# Industrial-Controller_MCU.net
KiCad netlist of a schematic drawn in Altium Designer
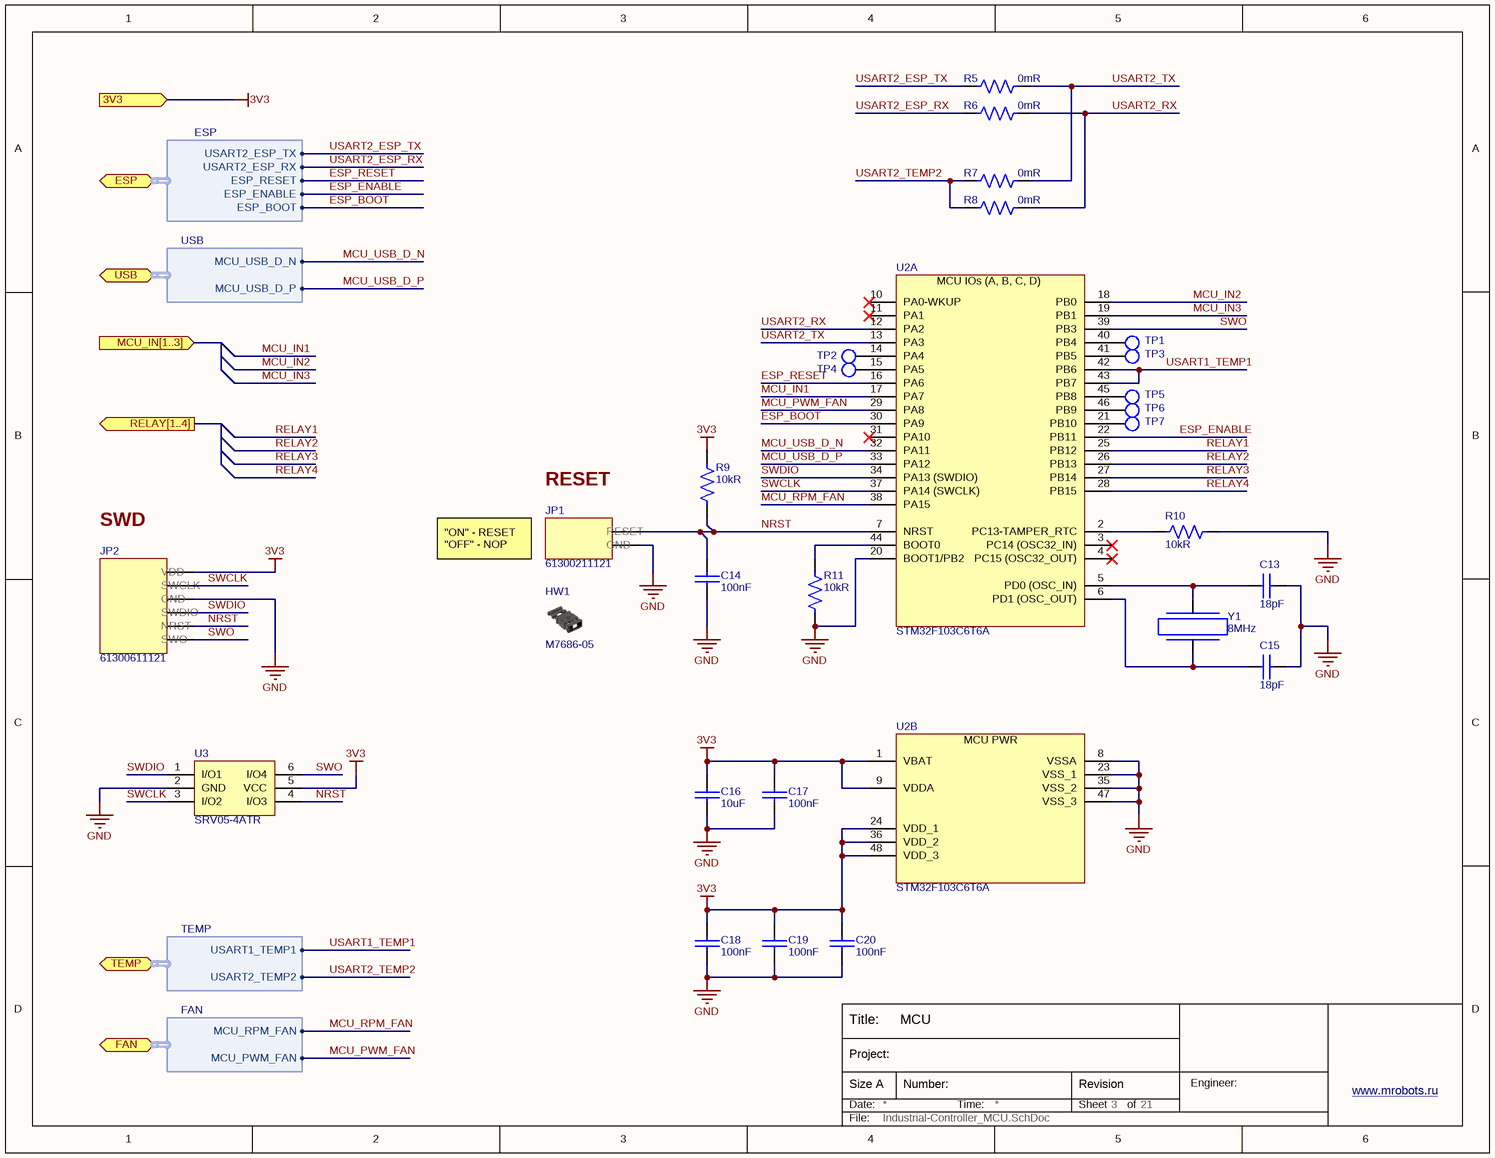
[diagram p0: Industrial-Controller_MCU.SchDoc]

(export (version "E")
  (design (tool "Eeschema 10.0.6"))
  (components
    (comp (ref "C13")
      (value "18pF")
      (footprint "CAP_0603")
      (description "CAP CER 18PF 50V C0G/NP0 0603")
      (fields
        (field (name "MANUFACTURER") "KEMET")
        (field (name "MANUFACTURER PART NUMBER") "C0603C180J5GACAUTO")
      )
      (libsource (lib "Industrial-Controller") (part "C0603C180J5GACAUTO"))
    )
    (comp (ref "C14")
      (value "100nF")
      (footprint "CAP_0603")
      (description "CAP CER 0.1UF 50V X7R 0603")
      (fields (field (name "TOLERANCE") "10%"))
      (libsource (lib "Industrial-Controller") (part "CL10B104KB8NNNL"))
    )
    (comp (ref "C15")
      (value "18pF")
      (footprint "CAP_0603")
      (description "CAP CER 18PF 50V C0G/NP0 0603")
      (fields
        (field (name "MANUFACTURER") "KEMET")
        (field (name "MANUFACTURER PART NUMBER") "C0603C180J5GACAUTO")
      )
      (libsource (lib "Industrial-Controller") (part "C0603C180J5GACAUTO"))
    )
    (comp (ref "C16")
      (value "10uF")
      (footprint "CAP_1210")
      (description "CAP CER 10UF 50V X7R 1210")
      (fields (field (name "TOLERANCE") "10%"))
      (libsource (lib "Industrial-Controller") (part "CL32B106KBJNNWE"))
    )
    (comp (ref "C17")
      (value "100nF")
      (footprint "CAP_0603")
      (description "CAP CER 0.1UF 50V X7R 0603")
      (fields (field (name "TOLERANCE") "10%"))
      (libsource (lib "Industrial-Controller") (part "CL10B104KB8NNNL"))
    )
    (comp (ref "C18")
      (value "100nF")
      (footprint "CAP_0603")
      (description "CAP CER 0.1UF 50V X7R 0603")
      (fields (field (name "TOLERANCE") "10%"))
      (libsource (lib "Industrial-Controller") (part "CL10B104KB8NNNL"))
    )
    (comp (ref "C19")
      (value "100nF")
      (footprint "CAP_0603")
      (description "CAP CER 0.1UF 50V X7R 0603")
      (fields (field (name "TOLERANCE") "10%"))
      (libsource (lib "Industrial-Controller") (part "CL10B104KB8NNNL"))
    )
    (comp (ref "C20")
      (value "100nF")
      (footprint "CAP_0603")
      (description "CAP CER 0.1UF 50V X7R 0603")
      (fields (field (name "TOLERANCE") "10%"))
      (libsource (lib "Industrial-Controller") (part "CL10B104KB8NNNL"))
    )
    (comp (ref "HW1")
      (value "M7686-05")
      (description "CLOSED TOP JUMPER SOCKET")
      (libsource (lib "Industrial-Controller") (part "M7686-05"))
    )
    (comp (ref "JP1")
      (value "61300211121")
      (footprint "PLS-2")
      (description "CONN HEADER VERT 2POS 2.54MM")
      (libsource (lib "Industrial-Controller") (part "61300211121"))
    )
    (comp (ref "JP2")
      (value "61300611121")
      (footprint "PLS-6")
      (description "CONN HEADER VERT 6POS 2.54MM")
      (libsource (lib "Industrial-Controller") (part "61300611121"))
    )
    (comp (ref "R5")
      (value "0mR")
      (footprint "RES_0603")
      (description "RES 0 OHM JUMPER 1/10W 0603")
      (fields (field (name "TOLERANCE") "1%"))
      (libsource (lib "Industrial-Controller") (part "RC0603FR-070RL"))
    )
    (comp (ref "R6")
      (value "0mR")
      (footprint "RES_0603")
      (description "RES 0 OHM JUMPER 1/10W 0603")
      (fields (field (name "TOLERANCE") "1%"))
      (libsource (lib "Industrial-Controller") (part "RC0603FR-070RL"))
    )
    (comp (ref "R7")
      (value "0mR")
      (footprint "RES_0603")
      (description "RES 0 OHM JUMPER 1/10W 0603")
      (fields (field (name "TOLERANCE") "1%"))
      (libsource (lib "Industrial-Controller") (part "RC0603FR-070RL"))
    )
    (comp (ref "R8")
      (value "0mR")
      (footprint "RES_0603")
      (description "RES 0 OHM JUMPER 1/10W 0603")
      (fields (field (name "TOLERANCE") "1%"))
      (libsource (lib "Industrial-Controller") (part "RC0603FR-070RL"))
    )
    (comp (ref "R9")
      (value "10kR")
      (footprint "RES_0603")
      (description "RES 10K OHM 1% 1/10W 0603")
      (fields (field (name "TOLERANCE") "1%"))
      (libsource (lib "Industrial-Controller") (part "RC0603FR-0710KL"))
    )
    (comp (ref "R10")
      (value "10kR")
      (footprint "RES_0603")
      (description "RES 10K OHM 1% 1/10W 0603")
      (fields (field (name "TOLERANCE") "1%"))
      (libsource (lib "Industrial-Controller") (part "RC0603FR-0710KL"))
    )
    (comp (ref "R11")
      (value "10kR")
      (footprint "RES_0603")
      (description "RES 10K OHM 1% 1/10W 0603")
      (fields (field (name "TOLERANCE") "1%"))
      (libsource (lib "Industrial-Controller") (part "RC0603FR-0710KL"))
    )
    (comp (ref "TP1")
      (value "TEST_POINT_SMT")
      (footprint "TEST_POINT_SMT")
      (description "STM TEST POINT")
      (libsource (lib "Industrial-Controller") (part "TEST_POINT_SMT"))
    )
    (comp (ref "TP2")
      (value "TEST_POINT_SMT")
      (footprint "TEST_POINT_SMT")
      (description "STM TEST POINT")
      (libsource (lib "Industrial-Controller") (part "TEST_POINT_SMT"))
    )
    (comp (ref "TP3")
      (value "TEST_POINT_SMT")
      (footprint "TEST_POINT_SMT")
      (description "STM TEST POINT")
      (libsource (lib "Industrial-Controller") (part "TEST_POINT_SMT"))
    )
    (comp (ref "TP4")
      (value "TEST_POINT_SMT")
      (footprint "TEST_POINT_SMT")
      (description "STM TEST POINT")
      (libsource (lib "Industrial-Controller") (part "TEST_POINT_SMT"))
    )
    (comp (ref "TP5")
      (value "TEST_POINT_SMT")
      (footprint "TEST_POINT_SMT")
      (description "STM TEST POINT")
      (libsource (lib "Industrial-Controller") (part "TEST_POINT_SMT"))
    )
    (comp (ref "TP6")
      (value "TEST_POINT_SMT")
      (footprint "TEST_POINT_SMT")
      (description "STM TEST POINT")
      (libsource (lib "Industrial-Controller") (part "TEST_POINT_SMT"))
    )
    (comp (ref "TP7")
      (value "TEST_POINT_SMT")
      (footprint "TEST_POINT_SMT")
      (description "STM TEST POINT")
      (libsource (lib "Industrial-Controller") (part "TEST_POINT_SMT"))
    )
    (comp (ref "U2")
      (value "STM32F103C6T6A")
      (footprint "LQFP48")
      (description "IC MCU 32BIT 32KB FLASH 48LQFP")
      (libsource (lib "Industrial-Controller") (part "STM32F103C6T6A"))
    )
    (comp (ref "U3")
      (value "SRV05-4ATR")
      (footprint "SOT-23-6")
      (description "TVS DIODE 5VWM 17.5VC SOT23-6")
      (libsource (lib "Industrial-Controller") (part "SRV05-4ATR"))
    )
    (comp (ref "Y1")
      (value "8MHz")
      (footprint "HC-49/US")
      (description "CRYSTAL 8.0000MHZ 18PF TH")
      (fields (field (name "TOLERANCE") "30ppm"))
      (libsource (lib "Industrial-Controller") (part "ATS080B-E"))
    )
  )
  (nets
    (net (code "5") (name "/ESP_BOOT") (class "Default")
      (node (ref "U2") (pin "30") (pinfunction "PA9_30") (pintype "passive"))
    )
    (net (code "6") (name "/ESP_ENABLE") (class "Default")
      (node (ref "U2") (pin "22") (pinfunction "PB11_22") (pintype "passive"))
    )
    (net (code "7") (name "/ESP_RESET") (class "Default")
      (node (ref "U2") (pin "16") (pinfunction "PA6_16") (pintype "passive"))
    )
    (net (code "8") (name "/MCU_IN1") (class "Default")
      (node (ref "U2") (pin "17") (pinfunction "PA7_17") (pintype "passive"))
    )
    (net (code "9") (name "/MCU_IN2") (class "Default")
      (node (ref "U2") (pin "18") (pinfunction "PB0_18") (pintype "passive"))
    )
    (net (code "10") (name "/MCU_IN3") (class "Default")
      (node (ref "U2") (pin "19") (pinfunction "PB1_19") (pintype "passive"))
    )
    (net (code "12") (name "/MCU_PWM_FAN") (class "Default")
      (node (ref "U2") (pin "29") (pinfunction "PA8_29") (pintype "passive"))
    )
    (net (code "13") (name "/MCU_RPM_FAN") (class "Default")
      (node (ref "U2") (pin "38") (pinfunction "PA15_38") (pintype "passive"))
    )
    (net (code "14") (name "/MCU_USB_D_N") (class "Default")
      (node (ref "U2") (pin "32") (pinfunction "PA11_32") (pintype "passive"))
    )
    (net (code "15") (name "/MCU_USB_D_P") (class "Default")
      (node (ref "U2") (pin "33") (pinfunction "PA12_33") (pintype "passive"))
    )
    (net (code "16") (name "/NRST") (class "Default")
      (node (ref "C14") (pin "1") (pinfunction "1_1") (pintype "passive"))
      (node (ref "JP1") (pin "1") (pinfunction "1_1") (pintype "passive"))
      (node (ref "JP2") (pin "5") (pinfunction "5_5") (pintype "passive"))
      (node (ref "R9") (pin "2") (pinfunction "2_2") (pintype "passive"))
      (node (ref "U2") (pin "7") (pinfunction "NRST_7") (pintype "passive"))
      (node (ref "U3") (pin "4") (pinfunction "I/O3_4") (pintype "passive"))
    )
    (net (code "17") (name "/RELAY1") (class "Default")
      (node (ref "U2") (pin "25") (pinfunction "PB12_25") (pintype "passive"))
    )
    (net (code "18") (name "/RELAY2") (class "Default")
      (node (ref "U2") (pin "26") (pinfunction "PB13_26") (pintype "passive"))
    )
    (net (code "19") (name "/RELAY3") (class "Default")
      (node (ref "U2") (pin "27") (pinfunction "PB14_27") (pintype "passive"))
    )
    (net (code "20") (name "/RELAY4") (class "Default")
      (node (ref "U2") (pin "28") (pinfunction "PB15_28") (pintype "passive"))
    )
    (net (code "22") (name "/SWCLK") (class "Default")
      (node (ref "JP2") (pin "2") (pinfunction "2_2") (pintype "passive"))
      (node (ref "U2") (pin "37") (pinfunction "PA14_(SWCLK)_37") (pintype "passive"))
      (node (ref "U3") (pin "3") (pinfunction "I/O2_3") (pintype "passive"))
    )
    (net (code "23") (name "/SWDIO") (class "Default")
      (node (ref "JP2") (pin "4") (pinfunction "4_4") (pintype "passive"))
      (node (ref "U2") (pin "34") (pinfunction "PA13_(SWDIO)_34") (pintype "passive"))
      (node (ref "U3") (pin "1") (pinfunction "I/O1_1") (pintype "passive"))
    )
    (net (code "24") (name "/SWO") (class "Default")
      (node (ref "JP2") (pin "6") (pinfunction "6_6") (pintype "passive"))
      (node (ref "U2") (pin "39") (pinfunction "PB3_39") (pintype "passive"))
      (node (ref "U3") (pin "6") (pinfunction "I/O4_6") (pintype "passive"))
    )
    (net (code "25") (name "/USART1_TEMP1") (class "Default")
      (node (ref "U2") (pin "42") (pinfunction "PB6_42") (pintype "passive"))
      (node (ref "U2") (pin "43") (pinfunction "PB7_43") (pintype "passive"))
    )
    (net (code "26") (name "/USART2_ESP_RX") (class "Default")
      (node (ref "R6") (pin "1") (pinfunction "1_1") (pintype "passive"))
    )
    (net (code "27") (name "/USART2_ESP_TX") (class "Default")
      (node (ref "R5") (pin "1") (pinfunction "1_1") (pintype "passive"))
    )
    (net (code "28") (name "/USART2_RX") (class "Default")
      (node (ref "R6") (pin "2") (pinfunction "2_2") (pintype "passive"))
      (node (ref "R8") (pin "2") (pinfunction "2_2") (pintype "passive"))
      (node (ref "U2") (pin "12") (pinfunction "PA2_12") (pintype "passive"))
    )
    (net (code "29") (name "/USART2_TEMP2") (class "Default")
      (node (ref "R7") (pin "1") (pinfunction "1_1") (pintype "passive"))
      (node (ref "R8") (pin "1") (pinfunction "1_1") (pintype "passive"))
    )
    (net (code "30") (name "/USART2_TX") (class "Default")
      (node (ref "R5") (pin "2") (pinfunction "2_2") (pintype "passive"))
      (node (ref "R7") (pin "2") (pinfunction "2_2") (pintype "passive"))
      (node (ref "U2") (pin "13") (pinfunction "PA3_13") (pintype "passive"))
    )
    (net (code "35") (name "3V3") (class "Default")
      (node (ref "C16") (pin "2") (pinfunction "2_2") (pintype "passive"))
      (node (ref "C17") (pin "1") (pinfunction "1_1") (pintype "passive"))
      (node (ref "C18") (pin "1") (pinfunction "1_1") (pintype "passive"))
      (node (ref "C19") (pin "1") (pinfunction "1_1") (pintype "passive"))
      (node (ref "C20") (pin "1") (pinfunction "1_1") (pintype "passive"))
      (node (ref "JP2") (pin "1") (pinfunction "1_1") (pintype "passive"))
      (node (ref "R9") (pin "1") (pinfunction "1_1") (pintype "passive"))
      (node (ref "U2") (pin "1") (pinfunction "VBAT_1") (pintype "passive"))
      (node (ref "U2") (pin "24") (pinfunction "VDD_1_24") (pintype "passive"))
      (node (ref "U2") (pin "36") (pinfunction "VDD_2_36") (pintype "passive"))
      (node (ref "U2") (pin "48") (pinfunction "VDD_3_48") (pintype "passive"))
      (node (ref "U2") (pin "9") (pinfunction "VDDA_9") (pintype "passive"))
      (node (ref "U3") (pin "5") (pinfunction "VCC_5") (pintype "passive"))
    )
    (net (code "36") (name "GND") (class "Default")
      (node (ref "C13") (pin "2") (pinfunction "2_2") (pintype "passive"))
      (node (ref "C14") (pin "2") (pinfunction "2_2") (pintype "passive"))
      (node (ref "C15") (pin "2") (pinfunction "2_2") (pintype "passive"))
      (node (ref "C16") (pin "1") (pinfunction "1_1") (pintype "passive"))
      (node (ref "C17") (pin "2") (pinfunction "2_2") (pintype "passive"))
      (node (ref "C18") (pin "2") (pinfunction "2_2") (pintype "passive"))
      (node (ref "C19") (pin "2") (pinfunction "2_2") (pintype "passive"))
      (node (ref "C20") (pin "2") (pinfunction "2_2") (pintype "passive"))
      (node (ref "JP1") (pin "2") (pinfunction "2_2") (pintype "passive"))
      (node (ref "JP2") (pin "3") (pinfunction "3_3") (pintype "passive"))
      (node (ref "R10") (pin "1") (pinfunction "1_1") (pintype "passive"))
      (node (ref "R11") (pin "1") (pinfunction "1_1") (pintype "passive"))
      (node (ref "U2") (pin "20") (pinfunction "BOOT1/PB2_20") (pintype "passive"))
      (node (ref "U2") (pin "23") (pinfunction "VSS_1_23") (pintype "passive"))
      (node (ref "U2") (pin "35") (pinfunction "VSS_2_35") (pintype "passive"))
      (node (ref "U2") (pin "47") (pinfunction "VSS_3_47") (pintype "passive"))
      (node (ref "U2") (pin "8") (pinfunction "VSSA_8") (pintype "passive"))
      (node (ref "U3") (pin "2") (pinfunction "GND_2") (pintype "passive"))
    )
    (net (code "37") (name "Net-(U2A-BOOT0)") (class "Default")
      (node (ref "R11") (pin "2") (pinfunction "2_2") (pintype "passive"))
      (node (ref "U2") (pin "44") (pinfunction "BOOT0_44") (pintype "passive"))
    )
    (net (code "38") (name "Net-(U2A-PA4)") (class "Default")
      (node (ref "TP2") (pin "1") (pinfunction "1_1") (pintype "passive"))
      (node (ref "U2") (pin "14") (pinfunction "PA4_14") (pintype "passive"))
    )
    (net (code "39") (name "Net-(U2A-PA5)") (class "Default")
      (node (ref "TP4") (pin "1") (pinfunction "1_1") (pintype "passive"))
      (node (ref "U2") (pin "15") (pinfunction "PA5_15") (pintype "passive"))
    )
    (net (code "40") (name "Net-(U2A-PB4)") (class "Default")
      (node (ref "TP1") (pin "1") (pinfunction "1_1") (pintype "passive"))
      (node (ref "U2") (pin "40") (pinfunction "PB4_40") (pintype "passive"))
    )
    (net (code "41") (name "Net-(U2A-PB5)") (class "Default")
      (node (ref "TP3") (pin "1") (pinfunction "1_1") (pintype "passive"))
      (node (ref "U2") (pin "41") (pinfunction "PB5_41") (pintype "passive"))
    )
    (net (code "42") (name "Net-(U2A-PB8)") (class "Default")
      (node (ref "TP5") (pin "1") (pinfunction "1_1") (pintype "passive"))
      (node (ref "U2") (pin "45") (pinfunction "PB8_45") (pintype "passive"))
    )
    (net (code "43") (name "Net-(U2A-PB9)") (class "Default")
      (node (ref "TP6") (pin "1") (pinfunction "1_1") (pintype "passive"))
      (node (ref "U2") (pin "46") (pinfunction "PB9_46") (pintype "passive"))
    )
    (net (code "44") (name "Net-(U2A-PB10)") (class "Default")
      (node (ref "TP7") (pin "1") (pinfunction "1_1") (pintype "passive"))
      (node (ref "U2") (pin "21") (pinfunction "PB10_21") (pintype "passive"))
    )
    (net (code "45") (name "Net-(U2A-PC13-TAMPER_RTC)") (class "Default")
      (node (ref "R10") (pin "2") (pinfunction "2_2") (pintype "passive"))
      (node (ref "U2") (pin "2") (pinfunction "PC13-TAMPER_RTC_2") (pintype "passive"))
    )
    (net (code "46") (name "Net-(U2A-PD0_(OSC_IN))") (class "Default")
      (node (ref "C13") (pin "1") (pinfunction "1_1") (pintype "passive"))
      (node (ref "U2") (pin "5") (pinfunction "PD0_(OSC_IN)_5") (pintype "passive"))
      (node (ref "Y1") (pin "2") (pinfunction "2_2") (pintype "passive"))
    )
    (net (code "47") (name "Net-(U2A-PD1_(OSC_OUT))") (class "Default")
      (node (ref "C15") (pin "1") (pinfunction "1_1") (pintype "passive"))
      (node (ref "U2") (pin "6") (pinfunction "PD1_(OSC_OUT)_6") (pintype "passive"))
      (node (ref "Y1") (pin "1") (pinfunction "1_1") (pintype "passive"))
    )
    (net (code "48") (name "unconnected-(U2A-PA0-WKUP-Pad10)") (class "Default")
      (node (ref "U2") (pin "10") (pinfunction "PA0-WKUP_10") (pintype "passive+no_connect"))
    )
    (net (code "49") (name "unconnected-(U2A-PA1-Pad11)") (class "Default")
      (node (ref "U2") (pin "11") (pinfunction "PA1_11") (pintype "passive+no_connect"))
    )
    (net (code "50") (name "unconnected-(U2A-PA10-Pad31)") (class "Default")
      (node (ref "U2") (pin "31") (pinfunction "PA10_31") (pintype "passive+no_connect"))
    )
    (net (code "51") (name "unconnected-(U2A-PC14_(OSC32_IN)-Pad3)") (class "Default")
      (node (ref "U2") (pin "3") (pinfunction "PC14_(OSC32_IN)_3") (pintype "passive+no_connect"))
    )
    (net (code "52") (name "unconnected-(U2A-PC15_(OSC32_OUT)-Pad4)") (class "Default")
      (node (ref "U2") (pin "4") (pinfunction "PC15_(OSC32_OUT)_4") (pintype "passive+no_connect"))
    )
  )
)
